# schematic.net
KiCad netlist of a schematic drawn in EAGLE
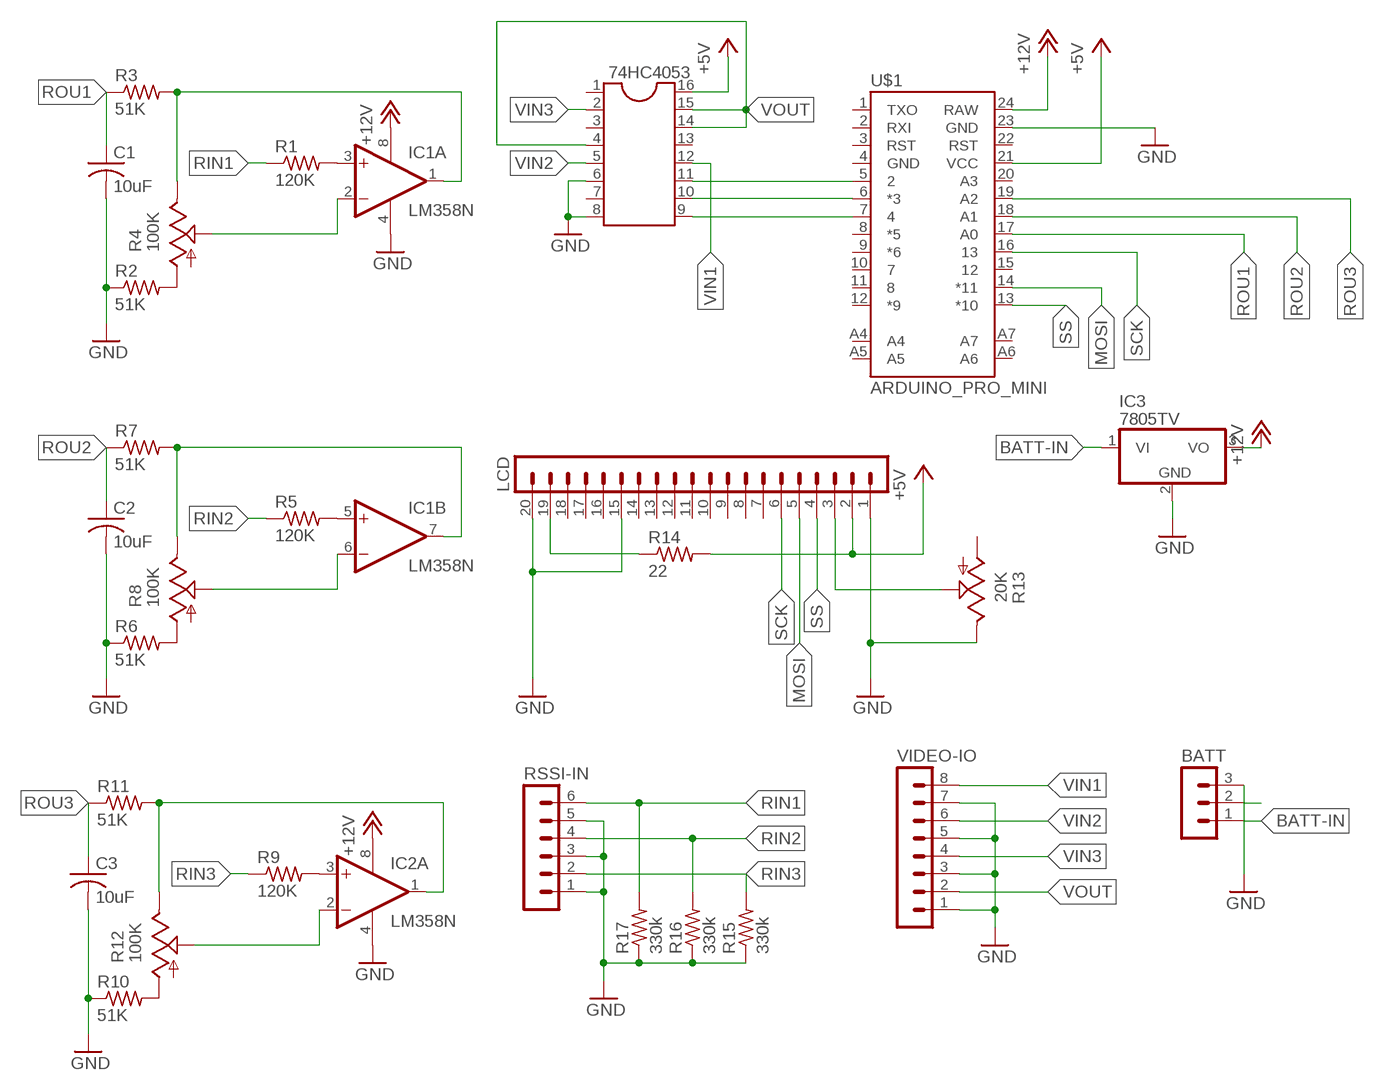
[diagram p0: schematic, sheet 1]

(export (version "E")
  (design (tool "Eeschema 10.0.6"))
  (components
    (comp (ref "74HC4053")
      (value "DIL16")
      (footprint "eagle-import:DIL16")
      (libsource (lib "eagle-import") (part "DIL16"))
    )
    (comp (ref "BATT")
      (value "MA03-1")
      (footprint "eagle-import:MA03-1")
      (libsource (lib "eagle-import") (part "MA03-1"))
    )
    (comp (ref "C1")
      (value "10uF")
      (footprint "eagle-import:C025-025X050")
      (libsource (lib "eagle-import") (part "C-US025-025X050"))
    )
    (comp (ref "C2")
      (value "10uF")
      (footprint "eagle-import:C025-025X050")
      (libsource (lib "eagle-import") (part "C-US025-025X050"))
    )
    (comp (ref "C3")
      (value "10uF")
      (footprint "eagle-import:C025-025X050")
      (libsource (lib "eagle-import") (part "C-US025-025X050"))
    )
    (comp (ref "IC1")
      (value "LM358N")
      (footprint "eagle-import:DIL08")
      (libsource (lib "eagle-import") (part "LM358N"))
    )
    (comp (ref "IC2")
      (value "LM358N")
      (footprint "eagle-import:DIL08")
      (libsource (lib "eagle-import") (part "LM358N"))
    )
    (comp (ref "IC3")
      (value "7805TV")
      (footprint "eagle-import:TO220V")
      (libsource (lib "eagle-import") (part "78TV05"))
    )
    (comp (ref "LCD")
      (value "MA20-1L")
      (footprint "eagle-import:MA20-1L")
      (libsource (lib "eagle-import") (part "MA20-1L"))
    )
    (comp (ref "R1")
      (value "120K")
      (footprint "eagle-import:0207_10")
      (libsource (lib "eagle-import") (part "R-US_0207/10"))
    )
    (comp (ref "R2")
      (value "51K")
      (footprint "eagle-import:0207_10")
      (libsource (lib "eagle-import") (part "R-US_0207/10"))
    )
    (comp (ref "R3")
      (value "51K")
      (footprint "eagle-import:0207_10")
      (libsource (lib "eagle-import") (part "R-US_0207/10"))
    )
    (comp (ref "R4")
      (value "100K")
      (footprint "eagle-import:S64W")
      (libsource (lib "eagle-import") (part "TRIM_US-S64W"))
    )
    (comp (ref "R5")
      (value "120K")
      (footprint "eagle-import:0207_10")
      (libsource (lib "eagle-import") (part "R-US_0207/10"))
    )
    (comp (ref "R6")
      (value "51K")
      (footprint "eagle-import:0207_10")
      (libsource (lib "eagle-import") (part "R-US_0207/10"))
    )
    (comp (ref "R7")
      (value "51K")
      (footprint "eagle-import:0207_10")
      (libsource (lib "eagle-import") (part "R-US_0207/10"))
    )
    (comp (ref "R8")
      (value "100K")
      (footprint "eagle-import:S64W")
      (libsource (lib "eagle-import") (part "TRIM_US-S64W"))
    )
    (comp (ref "R9")
      (value "120K")
      (footprint "eagle-import:0207_10")
      (libsource (lib "eagle-import") (part "R-US_0207/10"))
    )
    (comp (ref "R10")
      (value "51K")
      (footprint "eagle-import:0207_10")
      (libsource (lib "eagle-import") (part "R-US_0207/10"))
    )
    (comp (ref "R11")
      (value "51K")
      (footprint "eagle-import:0207_10")
      (libsource (lib "eagle-import") (part "R-US_0207/10"))
    )
    (comp (ref "R12")
      (value "100K")
      (footprint "eagle-import:S64W")
      (libsource (lib "eagle-import") (part "TRIM_US-S64W"))
    )
    (comp (ref "R13")
      (value "20K")
      (footprint "eagle-import:S64W")
      (libsource (lib "eagle-import") (part "TRIM_US-S64W"))
    )
    (comp (ref "R14")
      (value "22")
      (footprint "eagle-import:0207_10")
      (libsource (lib "eagle-import") (part "R-US_0207/10"))
    )
    (comp (ref "R15")
      (value "330k")
      (footprint "eagle-import:0207_10")
      (libsource (lib "eagle-import") (part "R-US_0207/10"))
    )
    (comp (ref "R16")
      (value "330k")
      (footprint "eagle-import:0207_10")
      (libsource (lib "eagle-import") (part "R-US_0207/10"))
    )
    (comp (ref "R17")
      (value "330k")
      (footprint "eagle-import:0207_10")
      (libsource (lib "eagle-import") (part "R-US_0207/10"))
    )
    (comp (ref "RSSI-IN")
      (value "MA06-1")
      (footprint "eagle-import:MA06-1")
      (libsource (lib "eagle-import") (part "MA06-1"))
    )
    (comp (ref "U$1")
      (value "ARDUINO_PRO_MINI")
      (footprint "eagle-import:ARDUINO_PRO_MINI")
      (libsource (lib "eagle-import") (part "ARDUINO_PRO_MINI"))
    )
    (comp (ref "VIDEO-IO")
      (value "MA08-1")
      (footprint "eagle-import:MA08-1")
      (libsource (lib "eagle-import") (part "MA08-1"))
    )
  )
  (nets
    (net (code "1") (name "+5V") (class "Default")
      (node (ref "74HC4053") (pin "16") (pinfunction "16_16") (pintype "passive"))
      (node (ref "LCD") (pin "2") (pinfunction "2_2") (pintype "passive"))
      (node (ref "R14") (pin "2") (pinfunction "2_2") (pintype "passive"))
      (node (ref "U$1") (pin "21") (pinfunction "VCC_21") (pintype "bidirectional"))
    )
    (net (code "2") (name "+12V") (class "Default")
      (node (ref "IC1") (pin "8") (pinfunction "V+_8") (pintype "power_in"))
      (node (ref "IC2") (pin "8") (pinfunction "V+_8") (pintype "power_in"))
      (node (ref "IC3") (pin "3") (pinfunction "VO_3") (pintype "passive"))
      (node (ref "U$1") (pin "24") (pinfunction "RAW_24") (pintype "bidirectional"))
    )
    (net (code "3") (name "BATT-IN") (class "Default")
      (node (ref "BATT") (pin "1") (pinfunction "1_1") (pintype "passive"))
      (node (ref "IC3") (pin "1") (pinfunction "VI_1") (pintype "input"))
    )
    (net (code "4") (name "GND") (class "Default")
      (node (ref "74HC4053") (pin "6") (pinfunction "6_6") (pintype "passive"))
      (node (ref "74HC4053") (pin "8") (pinfunction "8_8") (pintype "passive"))
      (node (ref "BATT") (pin "3") (pinfunction "3_3") (pintype "passive"))
      (node (ref "C1") (pin "2") (pinfunction "2_2") (pintype "passive"))
      (node (ref "C2") (pin "2") (pinfunction "2_2") (pintype "passive"))
      (node (ref "C3") (pin "2") (pinfunction "2_2") (pintype "passive"))
      (node (ref "IC1") (pin "4") (pinfunction "V-_4") (pintype "power_in"))
      (node (ref "IC2") (pin "4") (pinfunction "V-_4") (pintype "power_in"))
      (node (ref "IC3") (pin "2") (pinfunction "GND_2") (pintype "passive"))
      (node (ref "LCD") (pin "1") (pinfunction "1_1") (pintype "passive"))
      (node (ref "LCD") (pin "15") (pinfunction "15_15") (pintype "passive"))
      (node (ref "LCD") (pin "20") (pinfunction "20_20") (pintype "passive"))
      (node (ref "R10") (pin "1") (pinfunction "1_1") (pintype "passive"))
      (node (ref "R13") (pin "E") (pinfunction "E_E") (pintype "passive"))
      (node (ref "R15") (pin "1") (pinfunction "1_1") (pintype "passive"))
      (node (ref "R16") (pin "1") (pinfunction "1_1") (pintype "passive"))
      (node (ref "R17") (pin "1") (pinfunction "1_1") (pintype "passive"))
      (node (ref "R2") (pin "1") (pinfunction "1_1") (pintype "passive"))
      (node (ref "R6") (pin "1") (pinfunction "1_1") (pintype "passive"))
      (node (ref "RSSI-IN") (pin "1") (pinfunction "1_1") (pintype "passive"))
      (node (ref "RSSI-IN") (pin "3") (pinfunction "3_3") (pintype "passive"))
      (node (ref "RSSI-IN") (pin "5") (pinfunction "5_5") (pintype "passive"))
      (node (ref "U$1") (pin "23") (pinfunction "GND_23") (pintype "bidirectional"))
      (node (ref "VIDEO-IO") (pin "1") (pinfunction "1_1") (pintype "passive"))
      (node (ref "VIDEO-IO") (pin "3") (pinfunction "3_3") (pintype "passive"))
      (node (ref "VIDEO-IO") (pin "5") (pinfunction "5_5") (pintype "passive"))
      (node (ref "VIDEO-IO") (pin "7") (pinfunction "7_7") (pintype "passive"))
    )
    (net (code "5") (name "MOSI") (class "Default")
      (node (ref "LCD") (pin "5") (pinfunction "5_5") (pintype "passive"))
      (node (ref "U$1") (pin "14") (pinfunction "*11_14") (pintype "bidirectional"))
    )
    (net (code "6") (name "Net-(IC1A-+IN)") (class "Default")
      (node (ref "IC1") (pin "3") (pinfunction "+IN_3") (pintype "input"))
      (node (ref "R1") (pin "2") (pinfunction "2_2") (pintype "passive"))
    )
    (net (code "7") (name "Net-(IC1A--IN)") (class "Default")
      (node (ref "IC1") (pin "2") (pinfunction "-IN_2") (pintype "input"))
      (node (ref "R4") (pin "S") (pinfunction "S_S") (pintype "passive"))
    )
    (net (code "8") (name "Net-(IC1A-OUT)") (class "Default")
      (node (ref "IC1") (pin "1") (pinfunction "OUT_1") (pintype "output"))
      (node (ref "R3") (pin "2") (pinfunction "2_2") (pintype "passive"))
      (node (ref "R4") (pin "E") (pinfunction "E_E") (pintype "passive"))
    )
    (net (code "9") (name "Net-(IC1B-+IN)") (class "Default")
      (node (ref "IC1") (pin "5") (pinfunction "+IN_5") (pintype "input"))
      (node (ref "R5") (pin "2") (pinfunction "2_2") (pintype "passive"))
    )
    (net (code "10") (name "Net-(IC1B--IN)") (class "Default")
      (node (ref "IC1") (pin "6") (pinfunction "-IN_6") (pintype "input"))
      (node (ref "R8") (pin "S") (pinfunction "S_S") (pintype "passive"))
    )
    (net (code "11") (name "Net-(IC1B-OUT)") (class "Default")
      (node (ref "IC1") (pin "7") (pinfunction "OUT_7") (pintype "output"))
      (node (ref "R7") (pin "2") (pinfunction "2_2") (pintype "passive"))
      (node (ref "R8") (pin "E") (pinfunction "E_E") (pintype "passive"))
    )
    (net (code "12") (name "Net-(IC2A-+IN)") (class "Default")
      (node (ref "IC2") (pin "3") (pinfunction "+IN_3") (pintype "input"))
      (node (ref "R9") (pin "2") (pinfunction "2_2") (pintype "passive"))
    )
    (net (code "13") (name "Net-(IC2A--IN)") (class "Default")
      (node (ref "IC2") (pin "2") (pinfunction "-IN_2") (pintype "input"))
      (node (ref "R12") (pin "S") (pinfunction "S_S") (pintype "passive"))
    )
    (net (code "14") (name "Net-(IC2A-OUT)") (class "Default")
      (node (ref "IC2") (pin "1") (pinfunction "OUT_1") (pintype "output"))
      (node (ref "R11") (pin "2") (pinfunction "2_2") (pintype "passive"))
      (node (ref "R12") (pin "E") (pinfunction "E_E") (pintype "passive"))
    )
    (net (code "15") (name "Net-(LCD-Pad3)") (class "Default")
      (node (ref "LCD") (pin "3") (pinfunction "3_3") (pintype "passive"))
      (node (ref "R13") (pin "S") (pinfunction "S_S") (pintype "passive"))
    )
    (net (code "16") (name "Net-(LCD-Pad19)") (class "Default")
      (node (ref "LCD") (pin "19") (pinfunction "19_19") (pintype "passive"))
      (node (ref "R14") (pin "1") (pinfunction "1_1") (pintype "passive"))
    )
    (net (code "17") (name "Net-(R2-Pad2)") (class "Default")
      (node (ref "R2") (pin "2") (pinfunction "2_2") (pintype "passive"))
      (node (ref "R4") (pin "A") (pinfunction "A_A") (pintype "passive"))
    )
    (net (code "18") (name "Net-(R6-Pad2)") (class "Default")
      (node (ref "R6") (pin "2") (pinfunction "2_2") (pintype "passive"))
      (node (ref "R8") (pin "A") (pinfunction "A_A") (pintype "passive"))
    )
    (net (code "19") (name "Net-(R10-Pad2)") (class "Default")
      (node (ref "R10") (pin "2") (pinfunction "2_2") (pintype "passive"))
      (node (ref "R12") (pin "A") (pinfunction "A_A") (pintype "passive"))
    )
    (net (code "20") (name "Net-(U$1-*3)") (class "Default")
      (node (ref "74HC4053") (pin "10") (pinfunction "10_10") (pintype "passive"))
      (node (ref "U$1") (pin "6") (pinfunction "*3_6") (pintype "bidirectional"))
    )
    (net (code "21") (name "Net-(U$1-2)") (class "Default")
      (node (ref "74HC4053") (pin "11") (pinfunction "11_11") (pintype "passive"))
      (node (ref "U$1") (pin "5") (pinfunction "2_5") (pintype "bidirectional"))
    )
    (net (code "22") (name "Net-(U$1-4)") (class "Default")
      (node (ref "74HC4053") (pin "9") (pinfunction "9_9") (pintype "passive"))
      (node (ref "U$1") (pin "7") (pinfunction "4_7") (pintype "bidirectional"))
    )
    (net (code "23") (name "RIN1") (class "Default")
      (node (ref "R1") (pin "1") (pinfunction "1_1") (pintype "passive"))
      (node (ref "R17") (pin "2") (pinfunction "2_2") (pintype "passive"))
      (node (ref "RSSI-IN") (pin "6") (pinfunction "6_6") (pintype "passive"))
    )
    (net (code "24") (name "RIN2") (class "Default")
      (node (ref "R16") (pin "2") (pinfunction "2_2") (pintype "passive"))
      (node (ref "R5") (pin "1") (pinfunction "1_1") (pintype "passive"))
      (node (ref "RSSI-IN") (pin "4") (pinfunction "4_4") (pintype "passive"))
    )
    (net (code "25") (name "RIN3") (class "Default")
      (node (ref "R15") (pin "2") (pinfunction "2_2") (pintype "passive"))
      (node (ref "R9") (pin "1") (pinfunction "1_1") (pintype "passive"))
      (node (ref "RSSI-IN") (pin "2") (pinfunction "2_2") (pintype "passive"))
    )
    (net (code "26") (name "ROU1") (class "Default")
      (node (ref "C1") (pin "1") (pinfunction "1_1") (pintype "passive"))
      (node (ref "R3") (pin "1") (pinfunction "1_1") (pintype "passive"))
      (node (ref "U$1") (pin "17") (pinfunction "A0_17") (pintype "bidirectional"))
    )
    (net (code "27") (name "ROU2") (class "Default")
      (node (ref "C2") (pin "1") (pinfunction "1_1") (pintype "passive"))
      (node (ref "R7") (pin "1") (pinfunction "1_1") (pintype "passive"))
      (node (ref "U$1") (pin "18") (pinfunction "A1_18") (pintype "bidirectional"))
    )
    (net (code "28") (name "ROU3") (class "Default")
      (node (ref "C3") (pin "1") (pinfunction "1_1") (pintype "passive"))
      (node (ref "R11") (pin "1") (pinfunction "1_1") (pintype "passive"))
      (node (ref "U$1") (pin "19") (pinfunction "A2_19") (pintype "bidirectional"))
    )
    (net (code "29") (name "SCK") (class "Default")
      (node (ref "LCD") (pin "6") (pinfunction "6_6") (pintype "passive"))
      (node (ref "U$1") (pin "16") (pinfunction "13_16") (pintype "bidirectional"))
    )
    (net (code "30") (name "SS") (class "Default")
      (node (ref "LCD") (pin "4") (pinfunction "4_4") (pintype "passive"))
      (node (ref "U$1") (pin "13") (pinfunction "*10_13") (pintype "bidirectional"))
    )
    (net (code "31") (name "VIN1") (class "Default")
      (node (ref "74HC4053") (pin "12") (pinfunction "12_12") (pintype "passive"))
      (node (ref "VIDEO-IO") (pin "8") (pinfunction "8_8") (pintype "passive"))
    )
    (net (code "32") (name "VIN2") (class "Default")
      (node (ref "74HC4053") (pin "5") (pinfunction "5_5") (pintype "passive"))
      (node (ref "VIDEO-IO") (pin "6") (pinfunction "6_6") (pintype "passive"))
    )
    (net (code "33") (name "VIN3") (class "Default")
      (node (ref "74HC4053") (pin "2") (pinfunction "2_2") (pintype "passive"))
      (node (ref "VIDEO-IO") (pin "4") (pinfunction "4_4") (pintype "passive"))
    )
    (net (code "34") (name "VOUT") (class "Default")
      (node (ref "74HC4053") (pin "14") (pinfunction "14_14") (pintype "passive"))
      (node (ref "74HC4053") (pin "15") (pinfunction "15_15") (pintype "passive"))
      (node (ref "74HC4053") (pin "4") (pinfunction "4_4") (pintype "passive"))
      (node (ref "VIDEO-IO") (pin "2") (pinfunction "2_2") (pintype "passive"))
    )
    (net (code "35") (name "unconnected-(74HC4053-Pad1)") (class "Default")
      (node (ref "74HC4053") (pin "1") (pinfunction "1_1") (pintype "passive"))
    )
    (net (code "36") (name "unconnected-(74HC4053-Pad3)") (class "Default")
      (node (ref "74HC4053") (pin "3") (pinfunction "3_3") (pintype "passive"))
    )
    (net (code "37") (name "unconnected-(74HC4053-Pad7)") (class "Default")
      (node (ref "74HC4053") (pin "7") (pinfunction "7_7") (pintype "passive"))
    )
    (net (code "38") (name "unconnected-(74HC4053-Pad13)") (class "Default")
      (node (ref "74HC4053") (pin "13") (pinfunction "13_13") (pintype "passive"))
    )
    (net (code "39") (name "unconnected-(BATT-Pad2)") (class "Default")
      (node (ref "BATT") (pin "2") (pinfunction "2_2") (pintype "passive"))
    )
    (net (code "40") (name "unconnected-(LCD-Pad7)") (class "Default")
      (node (ref "LCD") (pin "7") (pinfunction "7_7") (pintype "passive"))
    )
    (net (code "41") (name "unconnected-(LCD-Pad8)") (class "Default")
      (node (ref "LCD") (pin "8") (pinfunction "8_8") (pintype "passive"))
    )
    (net (code "42") (name "unconnected-(LCD-Pad9)") (class "Default")
      (node (ref "LCD") (pin "9") (pinfunction "9_9") (pintype "passive"))
    )
    (net (code "43") (name "unconnected-(LCD-Pad10)") (class "Default")
      (node (ref "LCD") (pin "10") (pinfunction "10_10") (pintype "passive"))
    )
    (net (code "44") (name "unconnected-(LCD-Pad11)") (class "Default")
      (node (ref "LCD") (pin "11") (pinfunction "11_11") (pintype "passive"))
    )
    (net (code "45") (name "unconnected-(LCD-Pad12)") (class "Default")
      (node (ref "LCD") (pin "12") (pinfunction "12_12") (pintype "passive"))
    )
    (net (code "46") (name "unconnected-(LCD-Pad13)") (class "Default")
      (node (ref "LCD") (pin "13") (pinfunction "13_13") (pintype "passive"))
    )
    (net (code "47") (name "unconnected-(LCD-Pad14)") (class "Default")
      (node (ref "LCD") (pin "14") (pinfunction "14_14") (pintype "passive"))
    )
    (net (code "48") (name "unconnected-(LCD-Pad16)") (class "Default")
      (node (ref "LCD") (pin "16") (pinfunction "16_16") (pintype "passive"))
    )
    (net (code "49") (name "unconnected-(LCD-Pad17)") (class "Default")
      (node (ref "LCD") (pin "17") (pinfunction "17_17") (pintype "passive"))
    )
    (net (code "50") (name "unconnected-(LCD-Pad18)") (class "Default")
      (node (ref "LCD") (pin "18") (pinfunction "18_18") (pintype "passive"))
    )
    (net (code "51") (name "unconnected-(R13-PadA)") (class "Default")
      (node (ref "R13") (pin "A") (pinfunction "A_A") (pintype "passive"))
    )
    (net (code "52") (name "unconnected-(U$1-*5-Pad8)") (class "Default")
      (node (ref "U$1") (pin "8") (pinfunction "*5_8") (pintype "bidirectional"))
    )
    (net (code "53") (name "unconnected-(U$1-*6-Pad9)") (class "Default")
      (node (ref "U$1") (pin "9") (pinfunction "*6_9") (pintype "bidirectional"))
    )
    (net (code "54") (name "unconnected-(U$1-*9-Pad12)") (class "Default")
      (node (ref "U$1") (pin "12") (pinfunction "*9_12") (pintype "bidirectional"))
    )
    (net (code "55") (name "unconnected-(U$1-7-Pad10)") (class "Default")
      (node (ref "U$1") (pin "10") (pinfunction "7_10") (pintype "bidirectional"))
    )
    (net (code "56") (name "unconnected-(U$1-8-Pad11)") (class "Default")
      (node (ref "U$1") (pin "11") (pinfunction "8_11") (pintype "bidirectional"))
    )
    (net (code "57") (name "unconnected-(U$1-12-Pad15)") (class "Default")
      (node (ref "U$1") (pin "15") (pinfunction "12_15") (pintype "bidirectional"))
    )
    (net (code "58") (name "unconnected-(U$1-A3-Pad20)") (class "Default")
      (node (ref "U$1") (pin "20") (pinfunction "A3_20") (pintype "bidirectional"))
    )
    (net (code "59") (name "unconnected-(U$1-GND-Pad4)") (class "Default")
      (node (ref "U$1") (pin "4") (pinfunction "GND_4") (pintype "bidirectional"))
    )
    (net (code "60") (name "unconnected-(U$1-PadA4)") (class "Default")
      (node (ref "U$1") (pin "A4") (pinfunction "A4_A4") (pintype "bidirectional"))
    )
    (net (code "61") (name "unconnected-(U$1-PadA5)") (class "Default")
      (node (ref "U$1") (pin "A5") (pinfunction "A5_A5") (pintype "bidirectional"))
    )
    (net (code "62") (name "unconnected-(U$1-PadA6)") (class "Default")
      (node (ref "U$1") (pin "A6") (pinfunction "A6_A6") (pintype "bidirectional"))
    )
    (net (code "63") (name "unconnected-(U$1-PadA7)") (class "Default")
      (node (ref "U$1") (pin "A7") (pinfunction "A7_A7") (pintype "bidirectional"))
    )
    (net (code "64") (name "unconnected-(U$1-RST-Pad3)") (class "Default")
      (node (ref "U$1") (pin "3") (pinfunction "RST_3") (pintype "bidirectional"))
    )
    (net (code "65") (name "unconnected-(U$1-RST-Pad22)") (class "Default")
      (node (ref "U$1") (pin "22") (pinfunction "RST_22") (pintype "bidirectional"))
    )
    (net (code "66") (name "unconnected-(U$1-RXI-Pad2)") (class "Default")
      (node (ref "U$1") (pin "2") (pinfunction "RXI_2") (pintype "bidirectional"))
    )
    (net (code "67") (name "unconnected-(U$1-TXO-Pad1)") (class "Default")
      (node (ref "U$1") (pin "1") (pinfunction "TXO_1") (pintype "bidirectional"))
    )
  )
)
